# pump_driver_circuit.net
KiCad netlist of a schematic drawn in Altium Designer
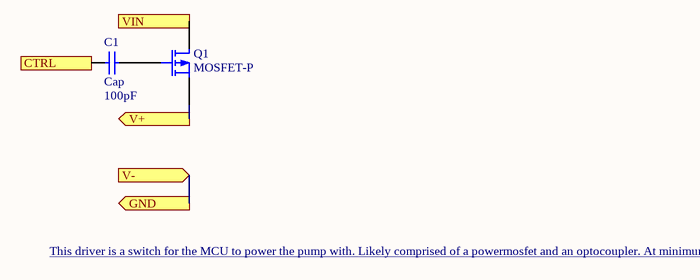
[diagram p0: pump_driver_circuit.SchDoc]

(export (version "E")
  (design (tool "Eeschema 10.0.6"))
  (components
    (comp (ref "C1")
      (value "Cap")
      (footprint "RAD-0.3")
      (description "Capacitor")
      (fields (field (name "ALTIUM_VALUE") "100pF") (field (name "PUBLISHER") "Altium Limited"))
      (libsource (lib "Miscellaneous Devices") (part "Cap"))
    )
    (comp (ref "Q1")
      (value "MOSFET-P")
      (footprint "E3")
      (description "P-Channel MOSFET")
      (fields (field (name "PUBLISHER") "Altium Limited"))
      (libsource (lib "Miscellaneous Devices") (part "MOSFET-P"))
    )
  )
  (nets
    (net (code "1") (name "/CTRL") (class "Default")
      (node (ref "C1") (pin "1") (pinfunction "1_1") (pintype "passive"))
    )
    (net (code "3") (name "/V+") (class "Default")
      (node (ref "Q1") (pin "3") (pinfunction "S_3") (pintype "passive"))
    )
    (net (code "4") (name "/VIN") (class "Default")
      (node (ref "Q1") (pin "1") (pinfunction "D_1") (pintype "passive"))
    )
    (net (code "5") (name "Net-(Q1-G)") (class "Default")
      (node (ref "C1") (pin "2") (pinfunction "2_2") (pintype "passive"))
      (node (ref "Q1") (pin "2") (pinfunction "G_2") (pintype "passive"))
    )
  )
)
